# piezo-buffer-and-preamp-ritter_V0-1.net
KiCad netlist of a schematic drawn in EAGLE
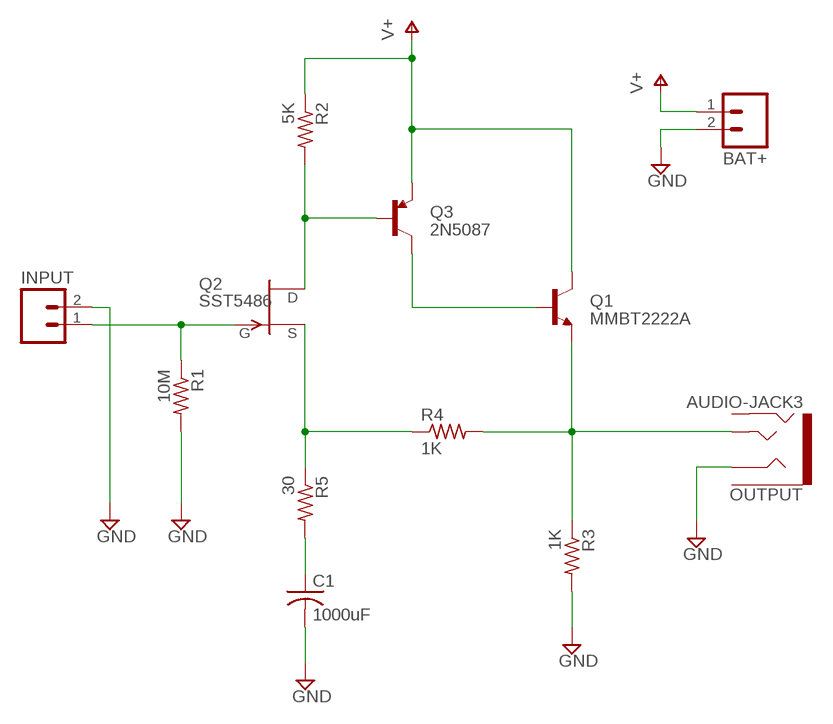
[diagram p0: schematic, sheet 1]

(export (version "E")
  (design (tool "Eeschema 10.0.6"))
  (components
    (comp (ref "BAT+")
      (value "M02LOCK")
      (footprint "eagle-import:1X02_LOCK")
      (libsource (lib "eagle-import") (part "M02LOCK"))
    )
    (comp (ref "C1")
      (value "1000uF")
      (footprint "eagle-import:C0805")
      (libsource (lib "eagle-import") (part "C-USC0805"))
    )
    (comp (ref "INPUT")
      (value "M02LOCK")
      (footprint "eagle-import:1X02_LOCK")
      (libsource (lib "eagle-import") (part "M02LOCK"))
    )
    (comp (ref "OUTPUT")
      (value "AUDIO-JACK3")
      (footprint "eagle-import:AUDIO-JACK-TRRS-SMD")
      (libsource (lib "eagle-import") (part "AUDIO-JACK3"))
    )
    (comp (ref "Q1")
      (value "MMBT2222A")
      (footprint "eagle-import:SOT23")
      (libsource (lib "eagle-import") (part "TRANSISTOR_NPN"))
    )
    (comp (ref "Q2")
      (value "SST5486")
      (footprint "eagle-import:SOT23")
      (libsource (lib "eagle-import") (part "?548SST6"))
    )
    (comp (ref "Q3")
      (value "2N5087")
      (footprint "eagle-import:SOT23")
      (libsource (lib "eagle-import") (part "TRANSISTOR_PNP"))
    )
    (comp (ref "R1")
      (value "10M")
      (footprint "eagle-import:R0805")
      (libsource (lib "eagle-import") (part "R-US_R0805"))
    )
    (comp (ref "R2")
      (value "5K")
      (footprint "eagle-import:R0805")
      (libsource (lib "eagle-import") (part "R-US_R0805"))
    )
    (comp (ref "R3")
      (value "1K")
      (footprint "eagle-import:R0805")
      (libsource (lib "eagle-import") (part "R-US_R0805"))
    )
    (comp (ref "R4")
      (value "1K")
      (footprint "eagle-import:R0805")
      (libsource (lib "eagle-import") (part "R-US_R0805"))
    )
    (comp (ref "R5")
      (value "30")
      (footprint "eagle-import:R0805")
      (libsource (lib "eagle-import") (part "R-US_R0805"))
    )
  )
  (nets
    (net (code "1") (name "GND") (class "Default")
      (node (ref "BAT+") (pin "2") (pinfunction "2_2") (pintype "passive"))
      (node (ref "C1") (pin "2") (pinfunction "2_2") (pintype "passive"))
      (node (ref "INPUT") (pin "2") (pinfunction "2_2") (pintype "passive"))
      (node (ref "OUTPUT") (pin "RING1") (pinfunction "RING1_RING1") (pintype "bidirectional"))
      (node (ref "R1") (pin "2") (pinfunction "2_2") (pintype "passive"))
      (node (ref "R3") (pin "2") (pinfunction "2_2") (pintype "passive"))
    )
    (net (code "2") (name "Net-(C1-Pad1)") (class "Default")
      (node (ref "C1") (pin "1") (pinfunction "1_1") (pintype "passive"))
      (node (ref "R5") (pin "2") (pinfunction "2_2") (pintype "passive"))
    )
    (net (code "3") (name "Net-(Q1-B)") (class "Default")
      (node (ref "Q1") (pin "1") (pinfunction "B_1") (pintype "passive"))
      (node (ref "Q3") (pin "3") (pinfunction "C_3") (pintype "passive"))
    )
    (net (code "4") (name "Net-(Q1-E)") (class "Default")
      (node (ref "OUTPUT") (pin "TIP") (pinfunction "TIP_TIP") (pintype "bidirectional"))
      (node (ref "Q1") (pin "2") (pinfunction "E_2") (pintype "passive"))
      (node (ref "R3") (pin "1") (pinfunction "1_1") (pintype "passive"))
      (node (ref "R4") (pin "2") (pinfunction "2_2") (pintype "passive"))
    )
    (net (code "5") (name "Net-(Q2-D)") (class "Default")
      (node (ref "Q2") (pin "1") (pinfunction "D_1") (pintype "passive"))
      (node (ref "Q3") (pin "1") (pinfunction "B_1") (pintype "passive"))
      (node (ref "R2") (pin "2") (pinfunction "2_2") (pintype "passive"))
    )
    (net (code "6") (name "Net-(Q2-G)") (class "Default")
      (node (ref "INPUT") (pin "1") (pinfunction "1_1") (pintype "passive"))
      (node (ref "Q2") (pin "3") (pinfunction "G_3") (pintype "passive"))
      (node (ref "R1") (pin "1") (pinfunction "1_1") (pintype "passive"))
    )
    (net (code "7") (name "Net-(Q2-S)") (class "Default")
      (node (ref "Q2") (pin "2") (pinfunction "S_2") (pintype "passive"))
      (node (ref "R4") (pin "1") (pinfunction "1_1") (pintype "passive"))
      (node (ref "R5") (pin "1") (pinfunction "1_1") (pintype "passive"))
    )
    (net (code "8") (name "V+") (class "Default")
      (node (ref "BAT+") (pin "1") (pinfunction "1_1") (pintype "passive"))
      (node (ref "Q1") (pin "3") (pinfunction "C_3") (pintype "passive"))
      (node (ref "Q3") (pin "2") (pinfunction "E_2") (pintype "passive"))
      (node (ref "R2") (pin "1") (pinfunction "1_1") (pintype "passive"))
    )
    (net (code "9") (name "unconnected-(OUTPUT-PadEARTH)") (class "Default")
      (node (ref "OUTPUT") (pin "EARTH") (pinfunction "EARTH_EARTH") (pintype "bidirectional"))
    )
    (net (code "10") (name "unconnected-(OUTPUT-PadRING2)") (class "Default")
      (node (ref "OUTPUT") (pin "RING2") (pinfunction "RING2_RING2") (pintype "bidirectional"))
    )
  )
)
